# BatteryMonitor.net
KiCad netlist of a schematic drawn in EAGLE
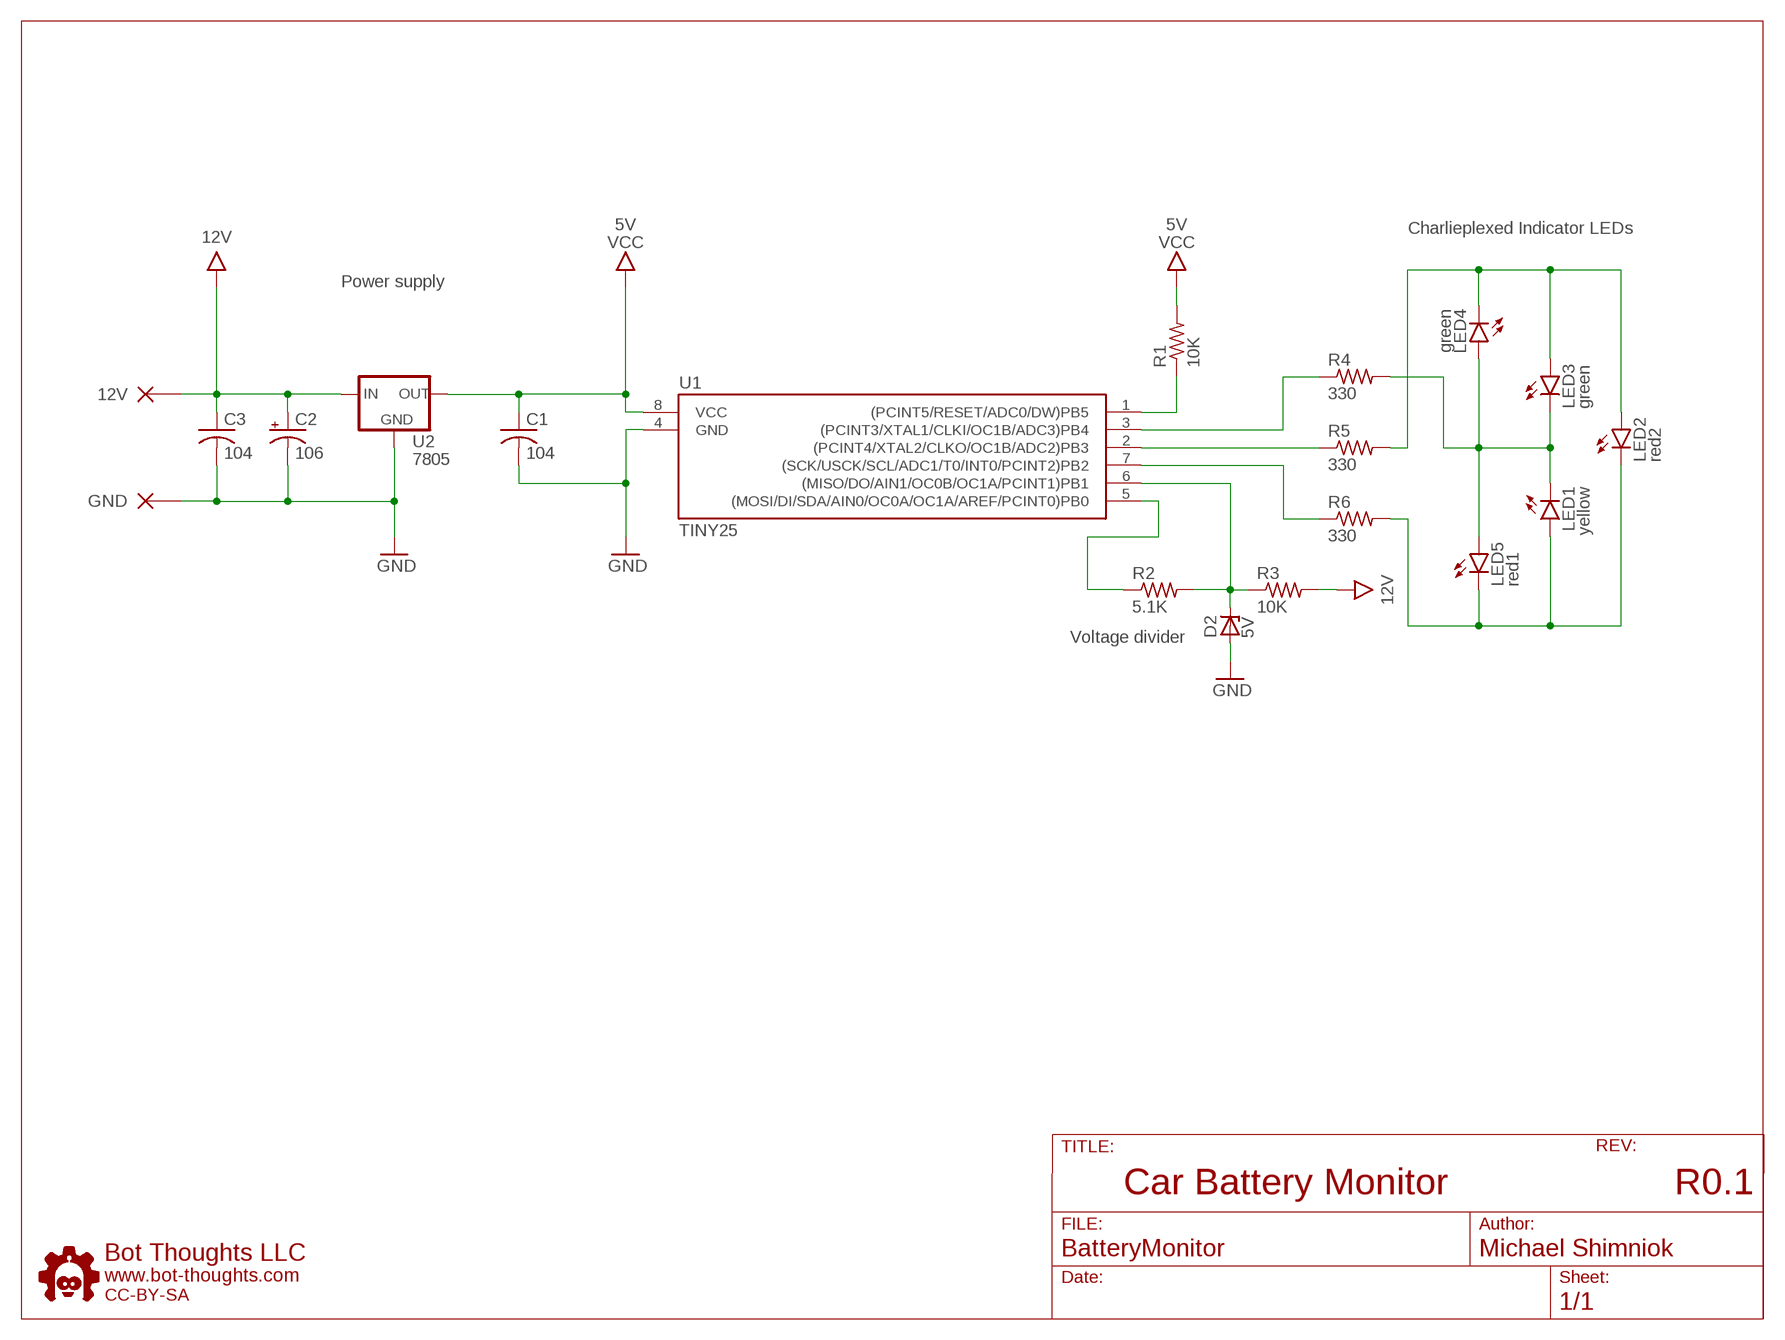
[diagram p0: schematic, sheet 1]

(export (version "E")
  (design (tool "Eeschema 10.0.6"))
  (components
    (comp (ref "C1")
      (value "104")
      (footprint "eagle-import:C050-024X044")
      (libsource (lib "eagle-import") (part "C-050PTH"))
    )
    (comp (ref "C2")
      (value "106")
      (footprint "eagle-import:E2,5-6")
      (libsource (lib "eagle-import") (part "CPOL-2.54-6MM"))
    )
    (comp (ref "C3")
      (value "104")
      (footprint "eagle-import:C025-024X044")
      (libsource (lib "eagle-import") (part "C-025PTH"))
    )
    (comp (ref "D2")
      (value "5V")
      (footprint "eagle-import:DO35Z7")
      (libsource (lib "eagle-import") (part "ZENER-DIODE-DO35"))
    )
    (comp (ref "LED1")
      (value "yellow")
      (footprint "eagle-import:LED5MMRA")
      (libsource (lib "eagle-import") (part "LED5MMRA"))
    )
    (comp (ref "LED2")
      (value "red2")
      (footprint "eagle-import:LED5MMRA")
      (libsource (lib "eagle-import") (part "LED5MMRA"))
    )
    (comp (ref "LED3")
      (value "green")
      (footprint "eagle-import:LED5MMRA")
      (libsource (lib "eagle-import") (part "LED5MMRA"))
    )
    (comp (ref "LED4")
      (value "green")
      (footprint "eagle-import:LED5MMRA")
      (libsource (lib "eagle-import") (part "LED5MMRA"))
    )
    (comp (ref "LED5")
      (value "red1")
      (footprint "eagle-import:LED5MMRA")
      (libsource (lib "eagle-import") (part "LED5MMRA"))
    )
    (comp (ref "R1")
      (value "10K")
      (footprint "eagle-import:0204_5")
      (libsource (lib "eagle-import") (part "R0204/5-PTH"))
    )
    (comp (ref "R2")
      (value "5.1K")
      (footprint "eagle-import:0204_5")
      (libsource (lib "eagle-import") (part "R0204/5-PTH"))
    )
    (comp (ref "R3")
      (value "10K")
      (footprint "eagle-import:0204_5")
      (libsource (lib "eagle-import") (part "R0204/5-PTH"))
    )
    (comp (ref "R4")
      (value "330")
      (footprint "eagle-import:0204_5")
      (libsource (lib "eagle-import") (part "R0204/5-PTH"))
    )
    (comp (ref "R5")
      (value "330")
      (footprint "eagle-import:0204_5")
      (libsource (lib "eagle-import") (part "R0204/5-PTH"))
    )
    (comp (ref "R6")
      (value "330")
      (footprint "eagle-import:0204_5")
      (libsource (lib "eagle-import") (part "R0204/5-PTH"))
    )
    (comp (ref "U$5")
      (value "BTLOGO-LOGO-MD")
      (footprint "eagle-import:BTLOGOM")
      (libsource (lib "eagle-import") (part "BTLOGO-LOGO-MD"))
    )
    (comp (ref "U1")
      (value "TINY25")
      (footprint "eagle-import:DIL08")
      (libsource (lib "eagle-import") (part "ATTINY45/85-MU"))
    )
    (comp (ref "U2")
      (value "7805")
      (footprint "eagle-import:TO220BH-NH")
      (libsource (lib "eagle-import") (part "78XX-TO220H-NH"))
    )
    (comp (ref "X1")
      (value "12V")
      (footprint "eagle-import:PAD_18GA")
      (libsource (lib "eagle-import") (part "WIREPAD_18GA"))
    )
    (comp (ref "X2")
      (value "GND")
      (footprint "eagle-import:PAD_18GA")
      (libsource (lib "eagle-import") (part "WIREPAD_18GA"))
    )
  )
  (nets
    (net (code "1") (name "5V") (class "Default")
      (node (ref "C1") (pin "1") (pinfunction "+_1") (pintype "passive"))
      (node (ref "R1") (pin "2") (pinfunction "2_2") (pintype "passive"))
      (node (ref "U1") (pin "8") (pinfunction "VCC_8") (pintype "power_in"))
      (node (ref "U2") (pin "3") (pinfunction "OUT_3") (pintype "passive"))
    )
    (net (code "2") (name "12V") (class "Default")
      (node (ref "C2") (pin "+") (pinfunction "+_+") (pintype "passive"))
      (node (ref "C3") (pin "1") (pinfunction "+_1") (pintype "passive"))
      (node (ref "R3") (pin "2") (pinfunction "2_2") (pintype "passive"))
      (node (ref "U2") (pin "1") (pinfunction "IN_1") (pintype "passive"))
      (node (ref "X1") (pin "P$1") (pinfunction "P_P$1") (pintype "bidirectional"))
    )
    (net (code "3") (name "GND") (class "Default")
      (node (ref "C1") (pin "2") (pinfunction "-_2") (pintype "passive"))
      (node (ref "C2") (pin "-") (pinfunction "-_-") (pintype "passive"))
      (node (ref "C3") (pin "2") (pinfunction "-_2") (pintype "passive"))
      (node (ref "D2") (pin "A") (pinfunction "A_A") (pintype "passive"))
      (node (ref "U1") (pin "4") (pinfunction "GND_4") (pintype "power_in"))
      (node (ref "U2") (pin "2") (pinfunction "GND_2") (pintype "passive"))
      (node (ref "X2") (pin "P$1") (pinfunction "P_P$1") (pintype "bidirectional"))
    )
    (net (code "4") (name "Net-(LED1-PadA)") (class "Default")
      (node (ref "LED1") (pin "A") (pinfunction "A_A") (pintype "passive"))
      (node (ref "LED2") (pin "C") (pinfunction "C_C") (pintype "passive"))
      (node (ref "LED5") (pin "C") (pinfunction "C_C") (pintype "passive"))
      (node (ref "R6") (pin "2") (pinfunction "2_2") (pintype "passive"))
    )
    (net (code "5") (name "Net-(LED1-PadC)") (class "Default")
      (node (ref "LED1") (pin "C") (pinfunction "C_C") (pintype "passive"))
      (node (ref "LED3") (pin "C") (pinfunction "C_C") (pintype "passive"))
      (node (ref "LED4") (pin "A") (pinfunction "A_A") (pintype "passive"))
      (node (ref "LED5") (pin "A") (pinfunction "A_A") (pintype "passive"))
      (node (ref "R4") (pin "2") (pinfunction "2_2") (pintype "passive"))
    )
    (net (code "6") (name "Net-(LED2-PadA)") (class "Default")
      (node (ref "LED2") (pin "A") (pinfunction "A_A") (pintype "passive"))
      (node (ref "LED3") (pin "A") (pinfunction "A_A") (pintype "passive"))
      (node (ref "LED4") (pin "C") (pinfunction "C_C") (pintype "passive"))
      (node (ref "R5") (pin "2") (pinfunction "2_2") (pintype "passive"))
    )
    (net (code "7") (name "Net-(U1-(MISO{slash}DO{slash}AIN1{slash}OC0B{slash}OC1A{slash}PCINT1)PB1)") (class "Default")
      (node (ref "D2") (pin "C") (pinfunction "C_C") (pintype "passive"))
      (node (ref "R2") (pin "2") (pinfunction "2_2") (pintype "passive"))
      (node (ref "R3") (pin "1") (pinfunction "1_1") (pintype "passive"))
      (node (ref "U1") (pin "6") (pinfunction "(MISO/DO/AIN1/OC0B/OC1A/PCINT1)PB1_6") (pintype "bidirectional"))
    )
    (net (code "8") (name "Net-(U1-(MOSI{slash}DI{slash}SDA{slash}AIN0{slash}OC0A{slash}OC1A{slash}AREF{slash}PCINT0)PB0)") (class "Default")
      (node (ref "R2") (pin "1") (pinfunction "1_1") (pintype "passive"))
      (node (ref "U1") (pin "5") (pinfunction "(MOSI/DI/SDA/AIN0/OC0A/OC1A/AREF/PCINT0)PB0_5") (pintype "bidirectional"))
    )
    (net (code "9") (name "Net-(U1-(PCINT3{slash}XTAL1{slash}CLKI{slash}OC1B{slash}ADC3)PB4)") (class "Default")
      (node (ref "R4") (pin "1") (pinfunction "1_1") (pintype "passive"))
      (node (ref "U1") (pin "3") (pinfunction "(PCINT3/XTAL1/CLKI/OC1B/ADC3)PB4_3") (pintype "bidirectional"))
    )
    (net (code "10") (name "Net-(U1-(PCINT4{slash}XTAL2{slash}CLKO{slash}OC1B{slash}ADC2)PB3)") (class "Default")
      (node (ref "R5") (pin "1") (pinfunction "1_1") (pintype "passive"))
      (node (ref "U1") (pin "2") (pinfunction "(PCINT4/XTAL2/CLKO/OC1B/ADC2)PB3_2") (pintype "bidirectional"))
    )
    (net (code "11") (name "Net-(U1-(PCINT5{slash}RESET{slash}ADC0{slash}DW)PB5)") (class "Default")
      (node (ref "R1") (pin "1") (pinfunction "1_1") (pintype "passive"))
      (node (ref "U1") (pin "1") (pinfunction "(PCINT5/RESET/ADC0/DW)PB5_1") (pintype "bidirectional"))
    )
    (net (code "12") (name "Net-(U1-(SCK{slash}USCK{slash}SCL{slash}ADC1{slash}T0{slash}INT0{slash}PCINT2)PB2)") (class "Default")
      (node (ref "R6") (pin "1") (pinfunction "1_1") (pintype "passive"))
      (node (ref "U1") (pin "7") (pinfunction "(SCK/USCK/SCL/ADC1/T0/INT0/PCINT2)PB2_7") (pintype "bidirectional"))
    )
  )
)
